# charge_controller.net
KiCad netlist of a schematic drawn in EAGLE
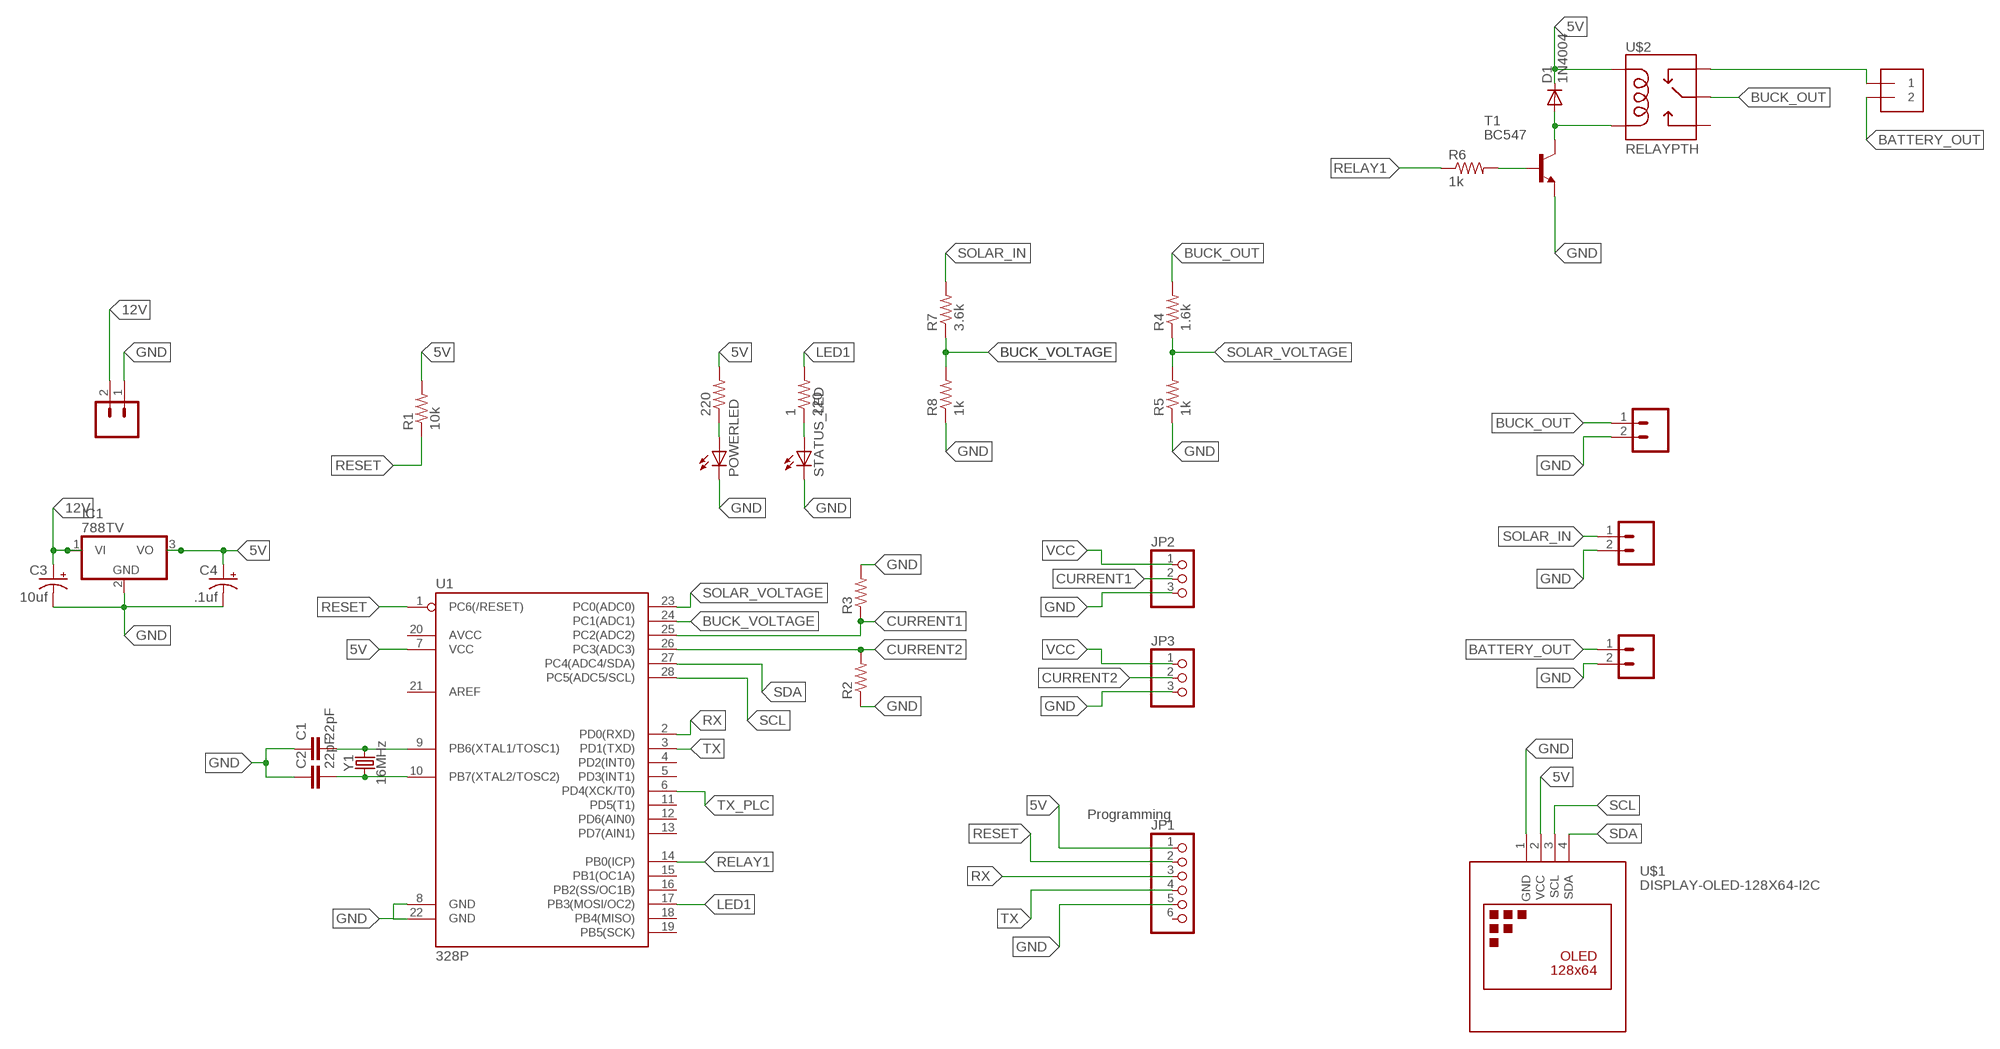
[diagram p0: schematic, sheet 1]

(export (version "E")
  (design (tool "Eeschema 10.0.6"))
  (components
    (comp (ref "1")
      (value "220")
      (footprint "eagle-import:0207_7")
      (libsource (lib "eagle-import") (part "R-US_0207/7"))
    )
    (comp (ref "220")
      (value "R-US_0207/7")
      (footprint "eagle-import:0207_7")
      (libsource (lib "eagle-import") (part "R-US_0207/7"))
    )
    (comp (ref "BATTERY-OUT")
      (value "CONN_025MM")
      (footprint "eagle-import:SCREWTERMINAL-5MM-2")
      (libsource (lib "eagle-import") (part "CONN_025MM"))
    )
    (comp (ref "BAT_OUT")
      (value "1X2-3.5MM")
      (footprint "eagle-import:1X2-3.5MM")
      (libsource (lib "eagle-import") (part "1X2-3.5MM"))
    )
    (comp (ref "BUCK-OUT")
      (value "CONN_025MM")
      (footprint "eagle-import:SCREWTERMINAL-5MM-2")
      (libsource (lib "eagle-import") (part "CONN_025MM"))
    )
    (comp (ref "C1")
      (value "22pF")
      (footprint "eagle-import:CAP-PTH-2.54")
      (libsource (lib "eagle-import") (part "22PF-PTH-2.54MM-200V-5%"))
    )
    (comp (ref "C2")
      (value "22pF")
      (footprint "eagle-import:CAP-PTH-2.54")
      (libsource (lib "eagle-import") (part "22PF-PTH-2.54MM-200V-5%"))
    )
    (comp (ref "C3")
      (value "10uf")
      (footprint "eagle-import:E5-5")
      (libsource (lib "eagle-import") (part "CPOL-USE5-5"))
    )
    (comp (ref "C4")
      (value ".1uf")
      (footprint "eagle-import:E5-5")
      (libsource (lib "eagle-import") (part "CPOL-USE5-5"))
    )
    (comp (ref "D1")
      (value "1N4004")
      (footprint "eagle-import:DO41-10")
      (libsource (lib "eagle-import") (part "1N4004"))
    )
    (comp (ref "IC1")
      (value "788TV")
      (footprint "eagle-import:TO220V")
      (libsource (lib "eagle-import") (part "78TV8"))
    )
    (comp (ref "J1")
      (value "CONN_025MM")
      (footprint "eagle-import:SCREWTERMINAL-5MM-2")
      (libsource (lib "eagle-import") (part "CONN_025MM"))
    )
    (comp (ref "JP1")
      (value "PINHD-1X6")
      (footprint "eagle-import:1X06")
      (libsource (lib "eagle-import") (part "PINHD-1X6"))
    )
    (comp (ref "JP2")
      (value "PINHD-1X3")
      (footprint "eagle-import:1X03")
      (libsource (lib "eagle-import") (part "PINHD-1X3"))
    )
    (comp (ref "JP3")
      (value "PINHD-1X3")
      (footprint "eagle-import:1X03")
      (libsource (lib "eagle-import") (part "PINHD-1X3"))
    )
    (comp (ref "POWERLED")
      (value "LED5MM")
      (footprint "eagle-import:LED5MM")
      (libsource (lib "eagle-import") (part "LED5MM"))
    )
    (comp (ref "R1")
      (value "10k")
      (footprint "eagle-import:0207_7")
      (libsource (lib "eagle-import") (part "R-US_0207/7"))
    )
    (comp (ref "R2")
      (value "R-US_0207/7")
      (footprint "eagle-import:0207_7")
      (libsource (lib "eagle-import") (part "R-US_0207/7"))
    )
    (comp (ref "R3")
      (value "R-US_0207/15")
      (footprint "eagle-import:0207_15")
      (libsource (lib "eagle-import") (part "R-US_0207/15"))
    )
    (comp (ref "R4")
      (value "1.6k")
      (footprint "eagle-import:0207_7")
      (libsource (lib "eagle-import") (part "R-US_0207/7"))
    )
    (comp (ref "R5")
      (value "1k")
      (footprint "eagle-import:0207_7")
      (libsource (lib "eagle-import") (part "R-US_0207/7"))
    )
    (comp (ref "R6")
      (value "1k")
      (footprint "eagle-import:0207_7")
      (libsource (lib "eagle-import") (part "R-US_0207/7"))
    )
    (comp (ref "R7")
      (value "3.6k")
      (footprint "eagle-import:0207_7")
      (libsource (lib "eagle-import") (part "R-US_0207/7"))
    )
    (comp (ref "R8")
      (value "1k")
      (footprint "eagle-import:0207_7")
      (libsource (lib "eagle-import") (part "R-US_0207/7"))
    )
    (comp (ref "SOLAR-IN")
      (value "CONN_025MM")
      (footprint "eagle-import:SCREWTERMINAL-5MM-2")
      (libsource (lib "eagle-import") (part "CONN_025MM"))
    )
    (comp (ref "STATUS_LED")
      (value "LED5MM")
      (footprint "eagle-import:LED5MM")
      (libsource (lib "eagle-import") (part "LED5MM"))
    )
    (comp (ref "T1")
      (value "BC547")
      (footprint "eagle-import:TO92")
      (libsource (lib "eagle-import") (part "BC547"))
    )
    (comp (ref "U$1")
      (value "DISPLAY-OLED-128X64-I2C")
      (footprint "eagle-import:DISPLAY-OLED-128X64-I2C")
      (libsource (lib "eagle-import") (part "DISPLAY-OLED-128X64-I2C"))
    )
    (comp (ref "U$2")
      (value "RELAYPTH")
      (footprint "eagle-import:SRD-05VDC-SL-C")
      (libsource (lib "eagle-import") (part "RELAYPTH"))
    )
    (comp (ref "U1")
      (value "328P")
      (footprint "eagle-import:DIP28")
      (libsource (lib "eagle-import") (part "ATMEGA328P_PDIP"))
    )
    (comp (ref "Y1")
      (value "16MHz")
      (footprint "eagle-import:HC49US")
      (libsource (lib "eagle-import") (part "CRYSTAL-16MHZPTH-HC49US"))
    )
  )
  (nets
    (net (code "1") (name "5V") (class "Default")
      (node (ref "220") (pin "2") (pinfunction "2_2") (pintype "passive"))
      (node (ref "C4") (pin "+") (pinfunction "+_+") (pintype "passive"))
      (node (ref "D1") (pin "C") (pinfunction "C_C") (pintype "passive"))
      (node (ref "IC1") (pin "3") (pinfunction "VO_3") (pintype "passive"))
      (node (ref "JP1") (pin "1") (pinfunction "1_1") (pintype "passive"))
      (node (ref "R1") (pin "2") (pinfunction "2_2") (pintype "passive"))
      (node (ref "U$1") (pin "2") (pinfunction "VCC_2") (pintype "power_in"))
      (node (ref "U$2") (pin "COIL1") (pinfunction "COIL1_COIL1") (pintype "bidirectional"))
      (node (ref "U1") (pin "7") (pinfunction "VCC_7") (pintype "bidirectional"))
    )
    (net (code "2") (name "12V") (class "Default")
      (node (ref "C3") (pin "+") (pinfunction "+_+") (pintype "passive"))
      (node (ref "IC1") (pin "1") (pinfunction "VI_1") (pintype "input"))
      (node (ref "J1") (pin "2") (pinfunction "2_2") (pintype "passive"))
    )
    (net (code "3") (name "BATTERY_OUT") (class "Default")
      (node (ref "BATTERY-OUT") (pin "1") (pinfunction "1_1") (pintype "passive"))
      (node (ref "BAT_OUT") (pin "2") (pinfunction "2_2") (pintype "passive"))
    )
    (net (code "4") (name "BUCK_OUT") (class "Default")
      (node (ref "BUCK-OUT") (pin "1") (pinfunction "1_1") (pintype "passive"))
      (node (ref "R4") (pin "2") (pinfunction "2_2") (pintype "passive"))
      (node (ref "U$2") (pin "SWCOMMON") (pinfunction "SWCOMMON_SWCOMMON") (pintype "bidirectional"))
    )
    (net (code "5") (name "BUCK_VOLTAGE") (class "Default")
      (node (ref "R7") (pin "1") (pinfunction "1_1") (pintype "passive"))
      (node (ref "R8") (pin "2") (pinfunction "2_2") (pintype "passive"))
      (node (ref "U1") (pin "24") (pinfunction "PC1(ADC1)_24") (pintype "bidirectional"))
    )
    (net (code "6") (name "CURRENT1") (class "Default")
      (node (ref "JP2") (pin "2") (pinfunction "2_2") (pintype "passive"))
      (node (ref "R3") (pin "1") (pinfunction "1_1") (pintype "passive"))
      (node (ref "U1") (pin "25") (pinfunction "PC2(ADC2)_25") (pintype "bidirectional"))
    )
    (net (code "7") (name "CURRENT2") (class "Default")
      (node (ref "JP3") (pin "2") (pinfunction "2_2") (pintype "passive"))
      (node (ref "R2") (pin "2") (pinfunction "2_2") (pintype "passive"))
      (node (ref "U1") (pin "26") (pinfunction "PC3(ADC3)_26") (pintype "bidirectional"))
    )
    (net (code "8") (name "GND") (class "Default")
      (node (ref "BATTERY-OUT") (pin "2") (pinfunction "2_2") (pintype "passive"))
      (node (ref "BUCK-OUT") (pin "2") (pinfunction "2_2") (pintype "passive"))
      (node (ref "C1") (pin "1") (pinfunction "1_1") (pintype "passive"))
      (node (ref "C2") (pin "1") (pinfunction "1_1") (pintype "passive"))
      (node (ref "C3") (pin "-") (pinfunction "-_-") (pintype "passive"))
      (node (ref "C4") (pin "-") (pinfunction "-_-") (pintype "passive"))
      (node (ref "IC1") (pin "2") (pinfunction "GND_2") (pintype "passive"))
      (node (ref "J1") (pin "1") (pinfunction "1_1") (pintype "passive"))
      (node (ref "JP1") (pin "5") (pinfunction "5_5") (pintype "passive"))
      (node (ref "JP2") (pin "3") (pinfunction "3_3") (pintype "passive"))
      (node (ref "JP3") (pin "3") (pinfunction "3_3") (pintype "passive"))
      (node (ref "POWERLED") (pin "K") (pinfunction "C_K") (pintype "passive"))
      (node (ref "R2") (pin "1") (pinfunction "1_1") (pintype "passive"))
      (node (ref "R3") (pin "2") (pinfunction "2_2") (pintype "passive"))
      (node (ref "R5") (pin "1") (pinfunction "1_1") (pintype "passive"))
      (node (ref "R8") (pin "1") (pinfunction "1_1") (pintype "passive"))
      (node (ref "SOLAR-IN") (pin "2") (pinfunction "2_2") (pintype "passive"))
      (node (ref "STATUS_LED") (pin "K") (pinfunction "C_K") (pintype "passive"))
      (node (ref "T1") (pin "1") (pinfunction "E_1") (pintype "passive"))
      (node (ref "U$1") (pin "1") (pinfunction "GND_1") (pintype "power_in"))
      (node (ref "U1") (pin "22") (pinfunction "GND_22") (pintype "bidirectional"))
      (node (ref "U1") (pin "8") (pinfunction "GND_8") (pintype "bidirectional"))
    )
    (net (code "9") (name "LED1") (class "Default")
      (node (ref "1") (pin "2") (pinfunction "2_2") (pintype "passive"))
      (node (ref "U1") (pin "17") (pinfunction "PB3(MOSI/OC2)_17") (pintype "bidirectional"))
    )
    (net (code "10") (name "Net-(1-Pad1)") (class "Default")
      (node (ref "1") (pin "1") (pinfunction "1_1") (pintype "passive"))
      (node (ref "STATUS_LED") (pin "A") (pinfunction "A_A") (pintype "passive"))
    )
    (net (code "11") (name "Net-(220-Pad1)") (class "Default")
      (node (ref "220") (pin "1") (pinfunction "1_1") (pintype "passive"))
      (node (ref "POWERLED") (pin "A") (pinfunction "A_A") (pintype "passive"))
    )
    (net (code "12") (name "Net-(T1-B)") (class "Default")
      (node (ref "R6") (pin "2") (pinfunction "2_2") (pintype "passive"))
      (node (ref "T1") (pin "2") (pinfunction "B_2") (pintype "passive"))
    )
    (net (code "13") (name "Net-(T1-C)") (class "Default")
      (node (ref "D1") (pin "A") (pinfunction "A_A") (pintype "passive"))
      (node (ref "T1") (pin "3") (pinfunction "C_3") (pintype "passive"))
      (node (ref "U$2") (pin "COIL0") (pinfunction "COIL0_COIL0") (pintype "bidirectional"))
    )
    (net (code "14") (name "Net-(U$2-SWCLOSE)") (class "Default")
      (node (ref "BAT_OUT") (pin "1") (pinfunction "1_1") (pintype "passive"))
      (node (ref "U$2") (pin "SWCLOSED") (pinfunction "SWCLOSE_SWCLOSED") (pintype "bidirectional"))
    )
    (net (code "15") (name "Net-(U1-PB6(XTAL1{slash}TOSC1))") (class "Default")
      (node (ref "C1") (pin "2") (pinfunction "2_2") (pintype "passive"))
      (node (ref "U1") (pin "9") (pinfunction "PB6(XTAL1/TOSC1)_9") (pintype "bidirectional"))
      (node (ref "Y1") (pin "2") (pinfunction "2_2") (pintype "passive"))
    )
    (net (code "16") (name "Net-(U1-PB7(XTAL2{slash}TOSC2))") (class "Default")
      (node (ref "C2") (pin "2") (pinfunction "2_2") (pintype "passive"))
      (node (ref "U1") (pin "10") (pinfunction "PB7(XTAL2/TOSC2)_10") (pintype "bidirectional"))
      (node (ref "Y1") (pin "1") (pinfunction "1_1") (pintype "passive"))
    )
    (net (code "17") (name "RELAY1") (class "Default")
      (node (ref "R6") (pin "1") (pinfunction "1_1") (pintype "passive"))
      (node (ref "U1") (pin "14") (pinfunction "PB0(ICP)_14") (pintype "bidirectional"))
    )
    (net (code "18") (name "RESET") (class "Default")
      (node (ref "JP1") (pin "2") (pinfunction "2_2") (pintype "passive"))
      (node (ref "R1") (pin "1") (pinfunction "1_1") (pintype "passive"))
      (node (ref "U1") (pin "1") (pinfunction "PC6(/RESET)_1") (pintype "bidirectional"))
    )
    (net (code "19") (name "RX") (class "Default")
      (node (ref "JP1") (pin "3") (pinfunction "3_3") (pintype "passive"))
      (node (ref "U1") (pin "2") (pinfunction "PD0(RXD)_2") (pintype "bidirectional"))
    )
    (net (code "20") (name "SCL") (class "Default")
      (node (ref "U$1") (pin "3") (pinfunction "SCL_3") (pintype "bidirectional"))
      (node (ref "U1") (pin "28") (pinfunction "PC5(ADC5/SCL)_28") (pintype "bidirectional"))
    )
    (net (code "21") (name "SDA") (class "Default")
      (node (ref "U$1") (pin "4") (pinfunction "SDA_4") (pintype "bidirectional"))
      (node (ref "U1") (pin "27") (pinfunction "PC4(ADC4/SDA)_27") (pintype "bidirectional"))
    )
    (net (code "22") (name "SOLAR_IN") (class "Default")
      (node (ref "R7") (pin "2") (pinfunction "2_2") (pintype "passive"))
      (node (ref "SOLAR-IN") (pin "1") (pinfunction "1_1") (pintype "passive"))
    )
    (net (code "23") (name "SOLAR_VOLTAGE") (class "Default")
      (node (ref "R4") (pin "1") (pinfunction "1_1") (pintype "passive"))
      (node (ref "R5") (pin "2") (pinfunction "2_2") (pintype "passive"))
      (node (ref "U1") (pin "23") (pinfunction "PC0(ADC0)_23") (pintype "bidirectional"))
    )
    (net (code "24") (name "TX") (class "Default")
      (node (ref "JP1") (pin "4") (pinfunction "4_4") (pintype "passive"))
      (node (ref "U1") (pin "3") (pinfunction "PD1(TXD)_3") (pintype "bidirectional"))
    )
    (net (code "25") (name "TX_PLC") (class "Default")
      (node (ref "U1") (pin "6") (pinfunction "PD4(XCK/T0)_6") (pintype "bidirectional"))
    )
    (net (code "26") (name "VCC") (class "Default")
      (node (ref "JP2") (pin "1") (pinfunction "1_1") (pintype "passive"))
      (node (ref "JP3") (pin "1") (pinfunction "1_1") (pintype "passive"))
    )
    (net (code "27") (name "unconnected-(JP1-Pad6)") (class "Default")
      (node (ref "JP1") (pin "6") (pinfunction "6_6") (pintype "passive"))
    )
    (net (code "28") (name "unconnected-(U$2-PadSWOPEN)") (class "Default")
      (node (ref "U$2") (pin "SWOPEN") (pinfunction "SWOPEN_SWOPEN") (pintype "bidirectional"))
    )
    (net (code "29") (name "unconnected-(U1-AREF-Pad21)") (class "Default")
      (node (ref "U1") (pin "21") (pinfunction "AREF_21") (pintype "bidirectional"))
    )
    (net (code "30") (name "unconnected-(U1-AVCC-Pad20)") (class "Default")
      (node (ref "U1") (pin "20") (pinfunction "AVCC_20") (pintype "bidirectional"))
    )
    (net (code "31") (name "unconnected-(U1-PB1(OC1A)-Pad15)") (class "Default")
      (node (ref "U1") (pin "15") (pinfunction "PB1(OC1A)_15") (pintype "bidirectional"))
    )
    (net (code "32") (name "unconnected-(U1-PB2(SS{slash}OC1B)-Pad16)") (class "Default")
      (node (ref "U1") (pin "16") (pinfunction "PB2(SS/OC1B)_16") (pintype "bidirectional"))
    )
    (net (code "33") (name "unconnected-(U1-PB4(MISO)-Pad18)") (class "Default")
      (node (ref "U1") (pin "18") (pinfunction "PB4(MISO)_18") (pintype "bidirectional"))
    )
    (net (code "34") (name "unconnected-(U1-PB5(SCK)-Pad19)") (class "Default")
      (node (ref "U1") (pin "19") (pinfunction "PB5(SCK)_19") (pintype "bidirectional"))
    )
    (net (code "35") (name "unconnected-(U1-PD2(INT0)-Pad4)") (class "Default")
      (node (ref "U1") (pin "4") (pinfunction "PD2(INT0)_4") (pintype "bidirectional"))
    )
    (net (code "36") (name "unconnected-(U1-PD3(INT1)-Pad5)") (class "Default")
      (node (ref "U1") (pin "5") (pinfunction "PD3(INT1)_5") (pintype "bidirectional"))
    )
    (net (code "37") (name "unconnected-(U1-PD5(T1)-Pad11)") (class "Default")
      (node (ref "U1") (pin "11") (pinfunction "PD5(T1)_11") (pintype "bidirectional"))
    )
    (net (code "38") (name "unconnected-(U1-PD6(AIN0)-Pad12)") (class "Default")
      (node (ref "U1") (pin "12") (pinfunction "PD6(AIN0)_12") (pintype "bidirectional"))
    )
    (net (code "39") (name "unconnected-(U1-PD7(AIN1)-Pad13)") (class "Default")
      (node (ref "U1") (pin "13") (pinfunction "PD7(AIN1)_13") (pintype "bidirectional"))
    )
  )
)
